# 20180513_Frontboard.net
KiCad netlist of a schematic drawn in EAGLE
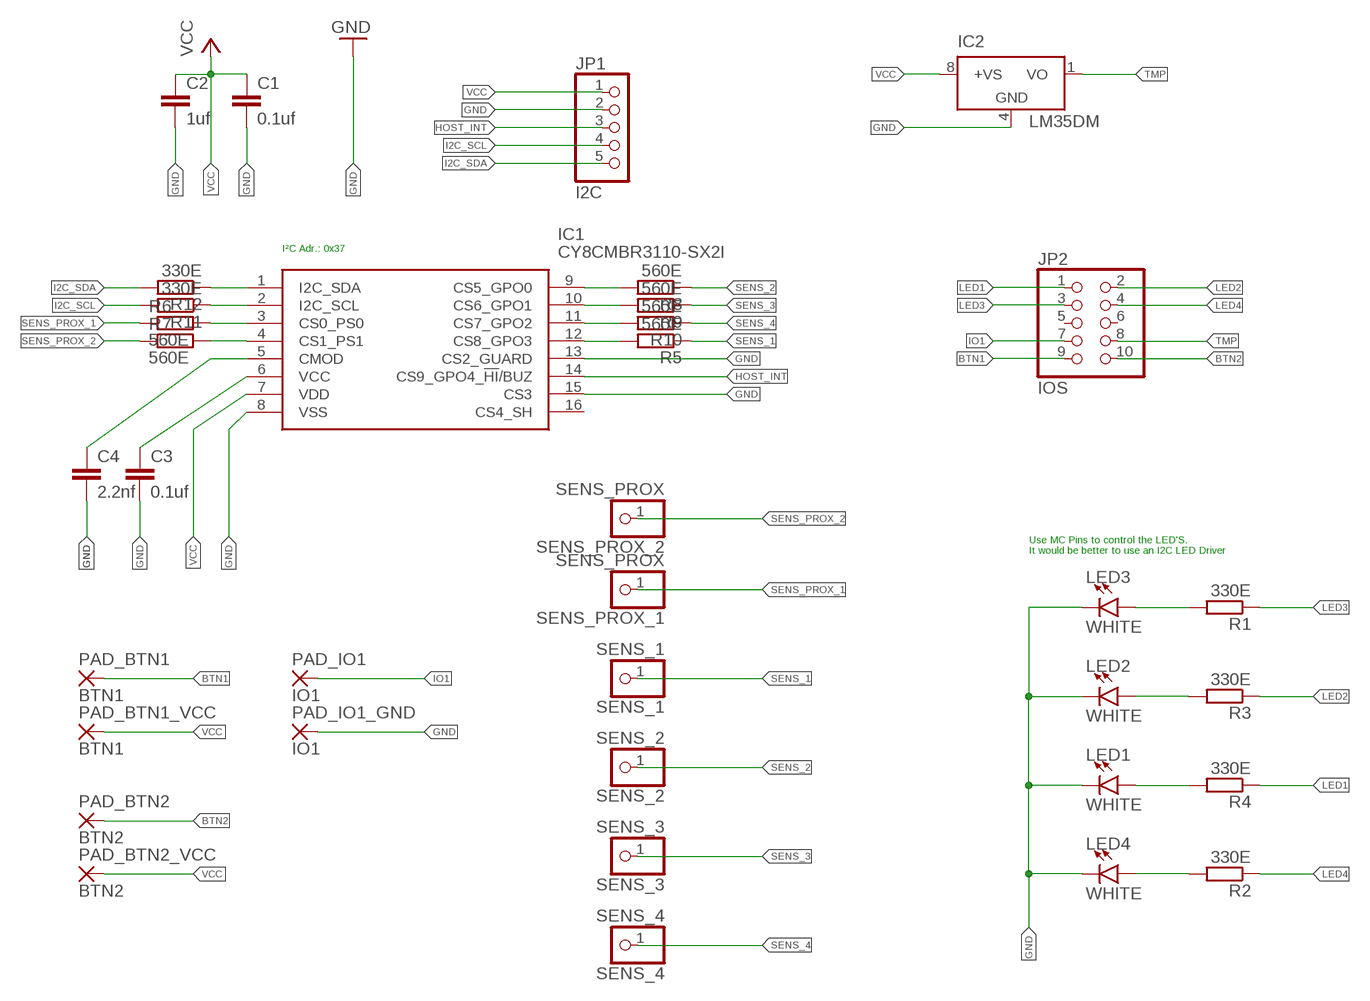
[diagram p0: schematic, sheet 1]

(export (version "E")
  (design (tool "Eeschema 10.0.6"))
  (components
    (comp (ref "C1")
      (value "0.1uf")
      (footprint "eagle-import:C0805")
      (libsource (lib "eagle-import") (part "C-EUC0805"))
    )
    (comp (ref "C2")
      (value "1uf")
      (footprint "eagle-import:C0805")
      (libsource (lib "eagle-import") (part "C-EUC0805"))
    )
    (comp (ref "C3")
      (value "0.1uf")
      (footprint "eagle-import:C0805")
      (libsource (lib "eagle-import") (part "C-EUC0805"))
    )
    (comp (ref "C4")
      (value "2.2nf")
      (footprint "eagle-import:C0805")
      (libsource (lib "eagle-import") (part "C-EUC0805"))
    )
    (comp (ref "IC1")
      (value "CY8CMBR3110-SX2I")
      (footprint "eagle-import:SOIC127P600X173-16N")
      (fields (field (name "RS_PART_NUMBER") "1242975P"))
      (libsource (lib "eagle-import") (part "CY8CMBR3110-SX2I"))
    )
    (comp (ref "IC2")
      (value "LM35DM")
      (footprint "eagle-import:SO08")
      (libsource (lib "eagle-import") (part "LM35DM"))
    )
    (comp (ref "JP1")
      (value "I2C")
      (footprint "eagle-import:1X05SMD")
      (libsource (lib "eagle-import") (part "PINHD-1X5_2.54-SMD"))
    )
    (comp (ref "JP2")
      (value "IOS")
      (footprint "eagle-import:2X05SMD")
      (libsource (lib "eagle-import") (part "PINHD-2X5_2.54-SMD"))
    )
    (comp (ref "LED1")
      (value "WHITE")
      (footprint "eagle-import:LED-1206-BOTTOM")
      (libsource (lib "eagle-import") (part "LED1206-BOTTOM"))
    )
    (comp (ref "LED2")
      (value "WHITE")
      (footprint "eagle-import:LED-1206-BOTTOM")
      (libsource (lib "eagle-import") (part "LED1206-BOTTOM"))
    )
    (comp (ref "LED3")
      (value "WHITE")
      (footprint "eagle-import:LED-1206-BOTTOM")
      (libsource (lib "eagle-import") (part "LED1206-BOTTOM"))
    )
    (comp (ref "LED4")
      (value "WHITE")
      (footprint "eagle-import:LED-1206-BOTTOM")
      (libsource (lib "eagle-import") (part "LED1206-BOTTOM"))
    )
    (comp (ref "PAD_BTN1")
      (value "BTN1")
      (footprint "eagle-import:2,54_1,0")
      (libsource (lib "eagle-import") (part "2,54/1,0"))
    )
    (comp (ref "PAD_BTN1_VCC")
      (value "BTN1")
      (footprint "eagle-import:2,54_1,0")
      (libsource (lib "eagle-import") (part "2,54/1,0"))
    )
    (comp (ref "PAD_BTN2")
      (value "BTN2")
      (footprint "eagle-import:2,54_1,0")
      (libsource (lib "eagle-import") (part "2,54/1,0"))
    )
    (comp (ref "PAD_BTN2_VCC")
      (value "BTN2")
      (footprint "eagle-import:2,54_1,0")
      (libsource (lib "eagle-import") (part "2,54/1,0"))
    )
    (comp (ref "PAD_IO1")
      (value "IO1")
      (footprint "eagle-import:2,54_1,0")
      (libsource (lib "eagle-import") (part "2,54/1,0"))
    )
    (comp (ref "PAD_IO1_GND")
      (value "IO1")
      (footprint "eagle-import:2,54_1,0")
      (libsource (lib "eagle-import") (part "2,54/1,0"))
    )
    (comp (ref "R1")
      (value "330E")
      (footprint "eagle-import:R0805")
      (libsource (lib "eagle-import") (part "R-EU_R0805"))
    )
    (comp (ref "R2")
      (value "330E")
      (footprint "eagle-import:R0805")
      (libsource (lib "eagle-import") (part "R-EU_R0805"))
    )
    (comp (ref "R3")
      (value "330E")
      (footprint "eagle-import:R0805")
      (libsource (lib "eagle-import") (part "R-EU_R0805"))
    )
    (comp (ref "R4")
      (value "330E")
      (footprint "eagle-import:R0805")
      (libsource (lib "eagle-import") (part "R-EU_R0805"))
    )
    (comp (ref "R5")
      (value "560E")
      (footprint "eagle-import:R0805")
      (libsource (lib "eagle-import") (part "R-EU_R0805"))
    )
    (comp (ref "R6")
      (value "560E")
      (footprint "eagle-import:R0805")
      (libsource (lib "eagle-import") (part "R-EU_R0805"))
    )
    (comp (ref "R7")
      (value "560E")
      (footprint "eagle-import:R0805")
      (libsource (lib "eagle-import") (part "R-EU_R0805"))
    )
    (comp (ref "R8")
      (value "560E")
      (footprint "eagle-import:R0805")
      (libsource (lib "eagle-import") (part "R-EU_R0805"))
    )
    (comp (ref "R9")
      (value "560E")
      (footprint "eagle-import:R0805")
      (libsource (lib "eagle-import") (part "R-EU_R0805"))
    )
    (comp (ref "R10")
      (value "560E")
      (footprint "eagle-import:R0805")
      (libsource (lib "eagle-import") (part "R-EU_R0805"))
    )
    (comp (ref "R11")
      (value "330E")
      (footprint "eagle-import:R0805")
      (libsource (lib "eagle-import") (part "R-EU_R0805"))
    )
    (comp (ref "R12")
      (value "330E")
      (footprint "eagle-import:R0805")
      (libsource (lib "eagle-import") (part "R-EU_R0805"))
    )
    (comp (ref "SENS_1")
      (value "SENS_1")
      (footprint "eagle-import:WPAD-1-0603")
      (libsource (lib "eagle-import") (part "WPAD-1-0603"))
    )
    (comp (ref "SENS_2")
      (value "SENS_2")
      (footprint "eagle-import:WPAD-1-0603")
      (libsource (lib "eagle-import") (part "WPAD-1-0603"))
    )
    (comp (ref "SENS_3")
      (value "SENS_3")
      (footprint "eagle-import:WPAD-1-0603")
      (libsource (lib "eagle-import") (part "WPAD-1-0603"))
    )
    (comp (ref "SENS_4")
      (value "SENS_4")
      (footprint "eagle-import:WPAD-1-0603")
      (libsource (lib "eagle-import") (part "WPAD-1-0603"))
    )
    (comp (ref "SENS_PROX_1")
      (value "SENS_PROX")
      (footprint "eagle-import:WPAD-1-0603")
      (libsource (lib "eagle-import") (part "WPAD-1-0603"))
    )
    (comp (ref "SENS_PROX_2")
      (value "SENS_PROX")
      (footprint "eagle-import:WPAD-1-0603")
      (libsource (lib "eagle-import") (part "WPAD-1-0603"))
    )
  )
  (nets
    (net (code "1") (name "BTN1") (class "Default")
      (node (ref "JP2") (pin "9") (pinfunction "9_9") (pintype "passive"))
      (node (ref "PAD_BTN1") (pin "1") (pinfunction "P_1") (pintype "passive"))
    )
    (net (code "2") (name "BTN2") (class "Default")
      (node (ref "JP2") (pin "10") (pinfunction "10_10") (pintype "passive"))
      (node (ref "PAD_BTN2") (pin "1") (pinfunction "P_1") (pintype "passive"))
    )
    (net (code "3") (name "GND") (class "Default")
      (node (ref "C1") (pin "2") (pinfunction "2_2") (pintype "passive"))
      (node (ref "C2") (pin "2") (pinfunction "2_2") (pintype "passive"))
      (node (ref "C3") (pin "2") (pinfunction "2_2") (pintype "passive"))
      (node (ref "C4") (pin "2") (pinfunction "2_2") (pintype "passive"))
      (node (ref "IC1") (pin "13") (pinfunction "CS2_GUARD_13") (pintype "bidirectional"))
      (node (ref "IC1") (pin "15") (pinfunction "CS3_15") (pintype "bidirectional"))
      (node (ref "IC1") (pin "8") (pinfunction "VSS_8") (pintype "bidirectional"))
      (node (ref "IC2") (pin "4") (pinfunction "GND_4") (pintype "power_in"))
      (node (ref "JP1") (pin "2") (pinfunction "2_2") (pintype "passive"))
      (node (ref "LED1") (pin "C") (pinfunction "C_C") (pintype "passive"))
      (node (ref "LED2") (pin "C") (pinfunction "C_C") (pintype "passive"))
      (node (ref "LED3") (pin "C") (pinfunction "C_C") (pintype "passive"))
      (node (ref "LED4") (pin "C") (pinfunction "C_C") (pintype "passive"))
      (node (ref "PAD_IO1_GND") (pin "1") (pinfunction "P_1") (pintype "passive"))
    )
    (net (code "4") (name "HOST_INT") (class "Default")
      (node (ref "IC1") (pin "14") (pinfunction "CS9_GPO4_~{HI}/BUZ_14") (pintype "bidirectional"))
      (node (ref "JP1") (pin "3") (pinfunction "3_3") (pintype "passive"))
    )
    (net (code "5") (name "I2C_SCL") (class "Default")
      (node (ref "JP1") (pin "4") (pinfunction "4_4") (pintype "passive"))
      (node (ref "R11") (pin "2") (pinfunction "2_2") (pintype "passive"))
    )
    (net (code "6") (name "I2C_SDA") (class "Default")
      (node (ref "JP1") (pin "5") (pinfunction "5_5") (pintype "passive"))
      (node (ref "R12") (pin "2") (pinfunction "2_2") (pintype "passive"))
    )
    (net (code "7") (name "IO1") (class "Default")
      (node (ref "JP2") (pin "7") (pinfunction "7_7") (pintype "passive"))
      (node (ref "PAD_IO1") (pin "1") (pinfunction "P_1") (pintype "passive"))
    )
    (net (code "8") (name "LED1") (class "Default")
      (node (ref "JP2") (pin "1") (pinfunction "1_1") (pintype "passive"))
      (node (ref "R4") (pin "1") (pinfunction "1_1") (pintype "passive"))
    )
    (net (code "9") (name "LED2") (class "Default")
      (node (ref "JP2") (pin "2") (pinfunction "2_2") (pintype "passive"))
      (node (ref "R3") (pin "1") (pinfunction "1_1") (pintype "passive"))
    )
    (net (code "10") (name "LED3") (class "Default")
      (node (ref "JP2") (pin "3") (pinfunction "3_3") (pintype "passive"))
      (node (ref "R1") (pin "1") (pinfunction "1_1") (pintype "passive"))
    )
    (net (code "11") (name "LED4") (class "Default")
      (node (ref "JP2") (pin "4") (pinfunction "4_4") (pintype "passive"))
      (node (ref "R2") (pin "1") (pinfunction "1_1") (pintype "passive"))
    )
    (net (code "12") (name "Net-(IC1-CMOD)") (class "Default")
      (node (ref "C4") (pin "1") (pinfunction "1_1") (pintype "passive"))
      (node (ref "IC1") (pin "5") (pinfunction "CMOD_5") (pintype "bidirectional"))
    )
    (net (code "13") (name "Net-(IC1-CS0_PS0)") (class "Default")
      (node (ref "IC1") (pin "3") (pinfunction "CS0_PS0_3") (pintype "bidirectional"))
      (node (ref "R6") (pin "2") (pinfunction "2_2") (pintype "passive"))
    )
    (net (code "14") (name "Net-(IC1-CS1_PS1)") (class "Default")
      (node (ref "IC1") (pin "4") (pinfunction "CS1_PS1_4") (pintype "bidirectional"))
      (node (ref "R7") (pin "2") (pinfunction "2_2") (pintype "passive"))
    )
    (net (code "15") (name "Net-(IC1-CS5_GPO0)") (class "Default")
      (node (ref "IC1") (pin "9") (pinfunction "CS5_GPO0_9") (pintype "bidirectional"))
      (node (ref "R8") (pin "2") (pinfunction "2_2") (pintype "passive"))
    )
    (net (code "16") (name "Net-(IC1-CS6_GPO1)") (class "Default")
      (node (ref "IC1") (pin "10") (pinfunction "CS6_GPO1_10") (pintype "bidirectional"))
      (node (ref "R9") (pin "2") (pinfunction "2_2") (pintype "passive"))
    )
    (net (code "17") (name "Net-(IC1-CS7_GPO2)") (class "Default")
      (node (ref "IC1") (pin "11") (pinfunction "CS7_GPO2_11") (pintype "bidirectional"))
      (node (ref "R10") (pin "2") (pinfunction "2_2") (pintype "passive"))
    )
    (net (code "18") (name "Net-(IC1-CS8_GPO3)") (class "Default")
      (node (ref "IC1") (pin "12") (pinfunction "CS8_GPO3_12") (pintype "bidirectional"))
      (node (ref "R5") (pin "2") (pinfunction "2_2") (pintype "passive"))
    )
    (net (code "19") (name "Net-(IC1-I2C_SCL)") (class "Default")
      (node (ref "IC1") (pin "2") (pinfunction "I2C_SCL_2") (pintype "bidirectional"))
      (node (ref "R11") (pin "1") (pinfunction "1_1") (pintype "passive"))
    )
    (net (code "20") (name "Net-(IC1-I2C_SDA)") (class "Default")
      (node (ref "IC1") (pin "1") (pinfunction "I2C_SDA_1") (pintype "bidirectional"))
      (node (ref "R12") (pin "1") (pinfunction "1_1") (pintype "passive"))
    )
    (net (code "21") (name "Net-(IC1-VCC)") (class "Default")
      (node (ref "C3") (pin "1") (pinfunction "1_1") (pintype "passive"))
      (node (ref "IC1") (pin "6") (pinfunction "VCC_6") (pintype "bidirectional"))
    )
    (net (code "22") (name "Net-(LED1-PadA)") (class "Default")
      (node (ref "LED1") (pin "A") (pinfunction "A_A") (pintype "passive"))
      (node (ref "R4") (pin "2") (pinfunction "2_2") (pintype "passive"))
    )
    (net (code "23") (name "Net-(LED2-PadA)") (class "Default")
      (node (ref "LED2") (pin "A") (pinfunction "A_A") (pintype "passive"))
      (node (ref "R3") (pin "2") (pinfunction "2_2") (pintype "passive"))
    )
    (net (code "24") (name "Net-(LED3-PadA)") (class "Default")
      (node (ref "LED3") (pin "A") (pinfunction "A_A") (pintype "passive"))
      (node (ref "R1") (pin "2") (pinfunction "2_2") (pintype "passive"))
    )
    (net (code "25") (name "Net-(LED4-PadA)") (class "Default")
      (node (ref "LED4") (pin "A") (pinfunction "A_A") (pintype "passive"))
      (node (ref "R2") (pin "2") (pinfunction "2_2") (pintype "passive"))
    )
    (net (code "26") (name "SENS_1") (class "Default")
      (node (ref "R5") (pin "1") (pinfunction "1_1") (pintype "passive"))
      (node (ref "SENS_1") (pin "1") (pinfunction "1_1") (pintype "passive"))
    )
    (net (code "27") (name "SENS_2") (class "Default")
      (node (ref "R8") (pin "1") (pinfunction "1_1") (pintype "passive"))
      (node (ref "SENS_2") (pin "1") (pinfunction "1_1") (pintype "passive"))
    )
    (net (code "28") (name "SENS_3") (class "Default")
      (node (ref "R9") (pin "1") (pinfunction "1_1") (pintype "passive"))
      (node (ref "SENS_3") (pin "1") (pinfunction "1_1") (pintype "passive"))
    )
    (net (code "29") (name "SENS_4") (class "Default")
      (node (ref "R10") (pin "1") (pinfunction "1_1") (pintype "passive"))
      (node (ref "SENS_4") (pin "1") (pinfunction "1_1") (pintype "passive"))
    )
    (net (code "30") (name "SENS_PROX_1") (class "Default")
      (node (ref "R6") (pin "1") (pinfunction "1_1") (pintype "passive"))
      (node (ref "SENS_PROX_1") (pin "1") (pinfunction "1_1") (pintype "passive"))
    )
    (net (code "31") (name "SENS_PROX_2") (class "Default")
      (node (ref "R7") (pin "1") (pinfunction "1_1") (pintype "passive"))
      (node (ref "SENS_PROX_2") (pin "1") (pinfunction "1_1") (pintype "passive"))
    )
    (net (code "32") (name "TMP") (class "Default")
      (node (ref "IC2") (pin "1") (pinfunction "VO_1") (pintype "input"))
      (node (ref "JP2") (pin "8") (pinfunction "8_8") (pintype "passive"))
    )
    (net (code "33") (name "VCC") (class "Default")
      (node (ref "C1") (pin "1") (pinfunction "1_1") (pintype "passive"))
      (node (ref "C2") (pin "1") (pinfunction "1_1") (pintype "passive"))
      (node (ref "IC1") (pin "7") (pinfunction "VDD_7") (pintype "bidirectional"))
      (node (ref "IC2") (pin "8") (pinfunction "+VS_8") (pintype "input"))
      (node (ref "JP1") (pin "1") (pinfunction "1_1") (pintype "passive"))
      (node (ref "PAD_BTN1_VCC") (pin "1") (pinfunction "P_1") (pintype "passive"))
      (node (ref "PAD_BTN2_VCC") (pin "1") (pinfunction "P_1") (pintype "passive"))
    )
    (net (code "34") (name "unconnected-(IC1-CS4_SH-Pad16)") (class "Default")
      (node (ref "IC1") (pin "16") (pinfunction "CS4_SH_16") (pintype "bidirectional"))
    )
    (net (code "35") (name "unconnected-(JP2-Pad5)") (class "Default")
      (node (ref "JP2") (pin "5") (pinfunction "5_5") (pintype "passive"))
    )
    (net (code "36") (name "unconnected-(JP2-Pad6)") (class "Default")
      (node (ref "JP2") (pin "6") (pinfunction "6_6") (pintype "passive"))
    )
  )
)
